# PERIPHERALS.net
KiCad netlist of a schematic drawn in Altium Designer
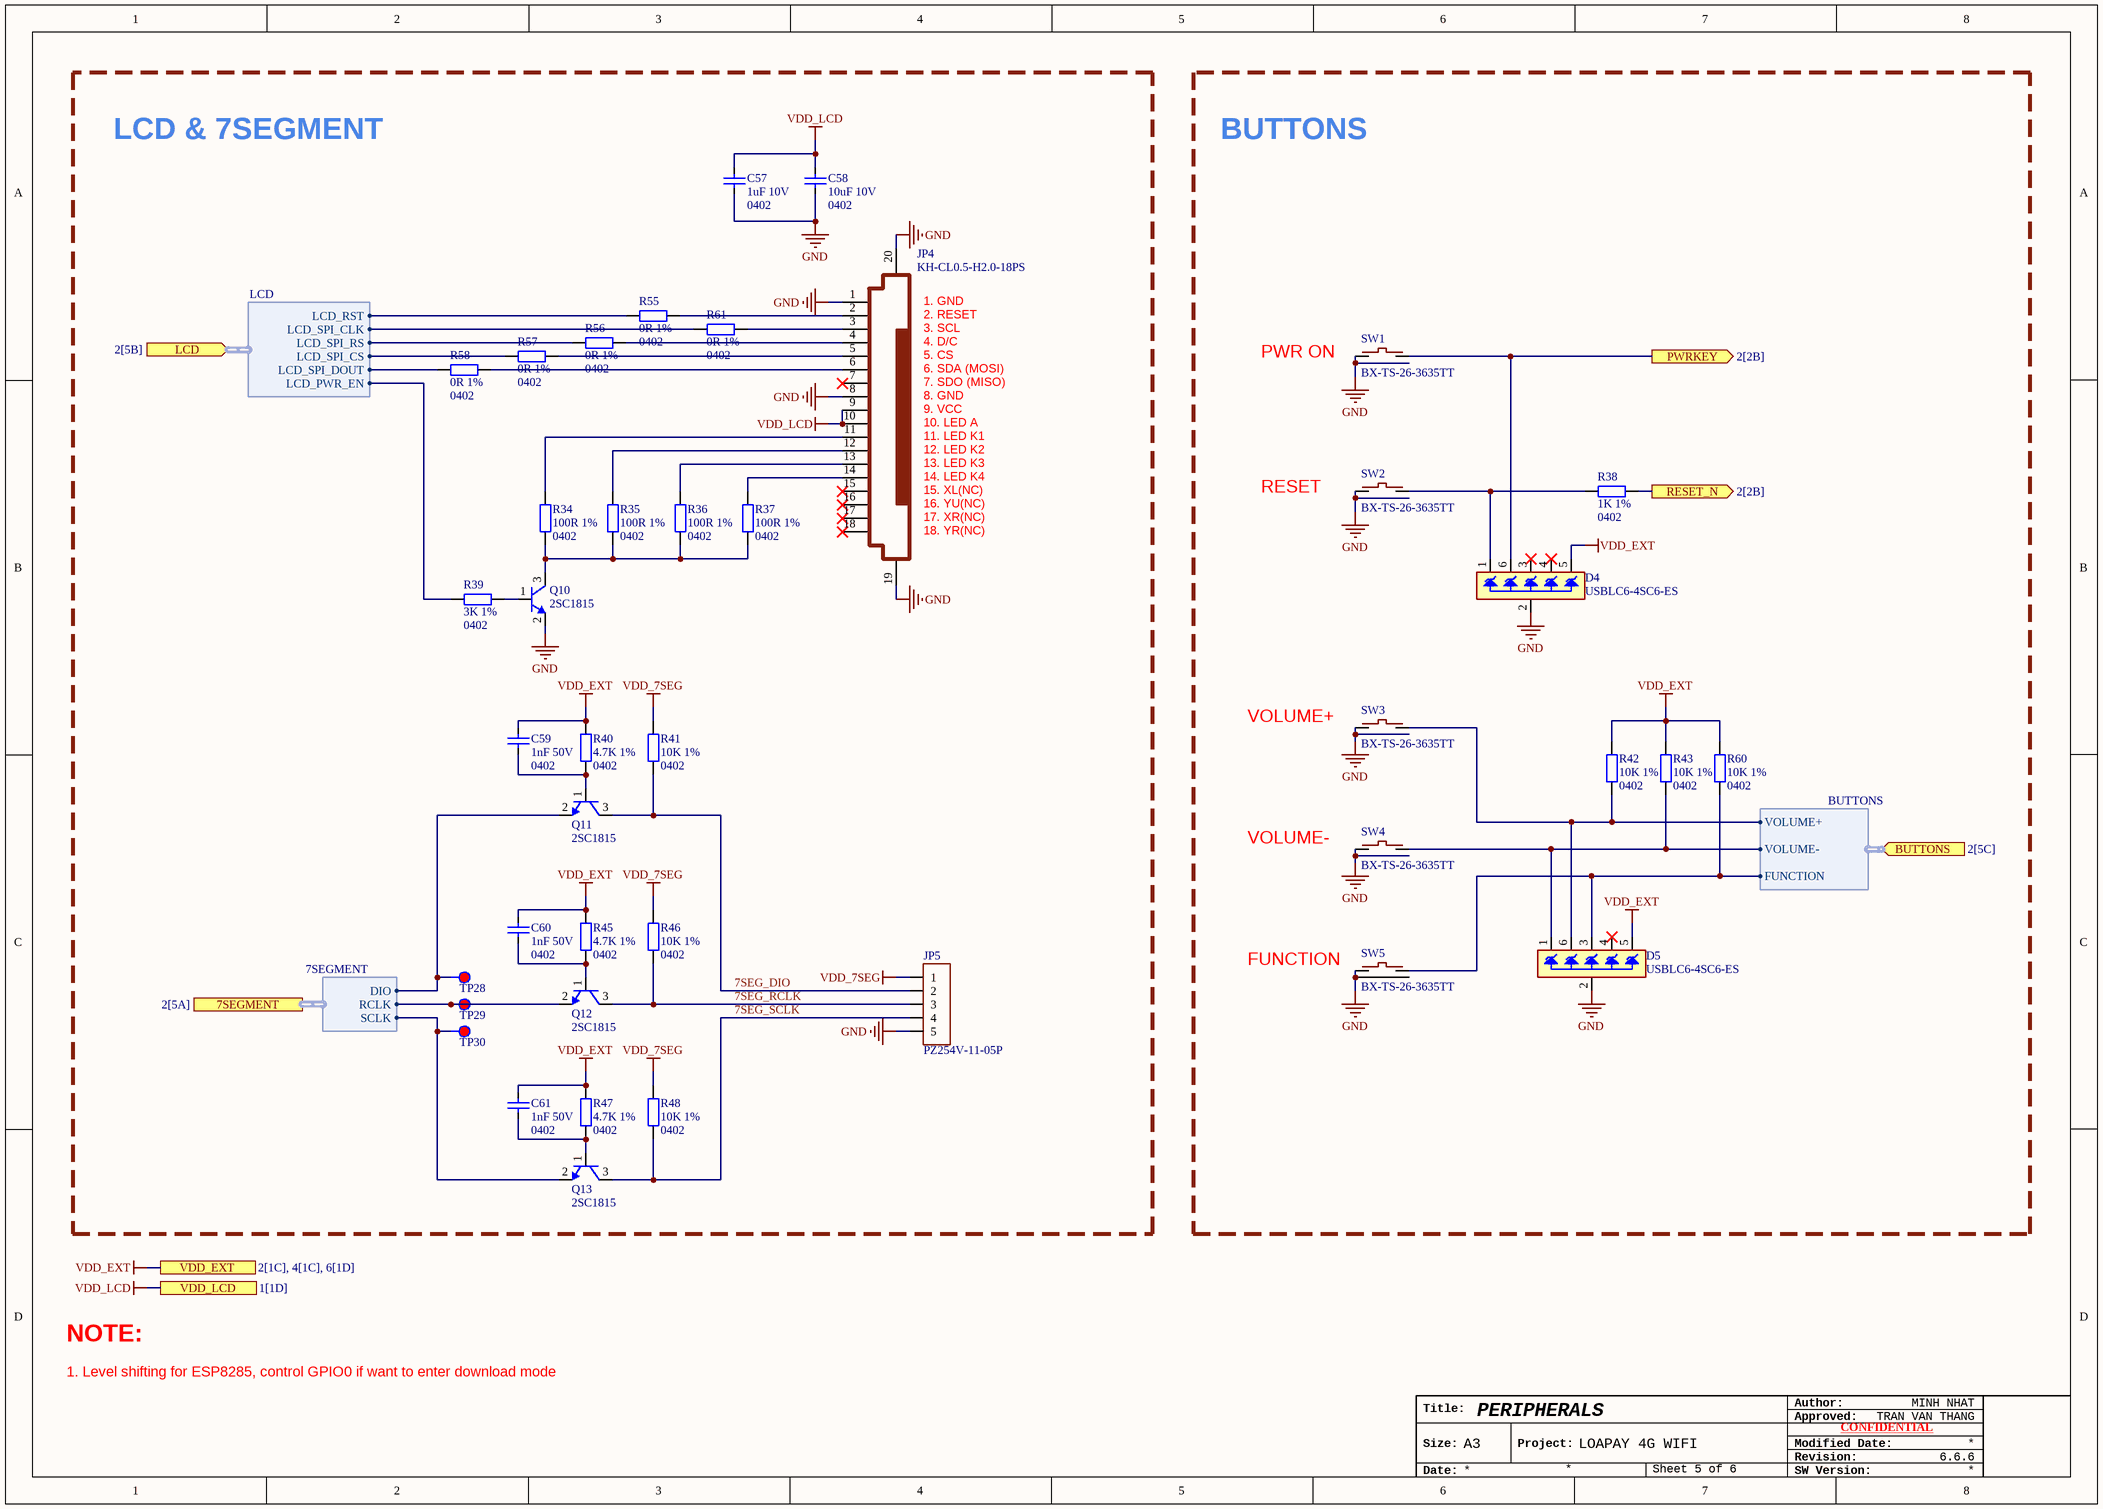
[diagram p0: PERIPHERALS.SchDoc]

(export (version "E")
  (design (tool "Eeschema 10.0.6"))
  (components
    (comp (ref "C57")
      (value "1uF 10V")
      (footprint "C0402_2")
      (description "10V 1uF X5R ±10% 0402 Multilayer Ceramic Capacitors MLCC - SMD/SMT ROHS")
      (fields
        (field (name "MANUFACTURER") "Samsung Electro-Mechanics")
        (field (name "MANUFACTURE PART NUMBER") "CL05A105KP5NNNC")
        (field (name "PACKAGE") "0402")
      )
      (libsource (lib "Capacitor") (part "C0402_MLCC_1uF_10V"))
    )
    (comp (ref "C58")
      (value "10uF 10V")
      (footprint "C0402_2")
      (description "10V 10uF X5R ±20% 0402 Multilayer Ceramic Capacitors MLCC - SMD/SMT ROHS")
      (fields
        (field (name "MANUFACTURER") "Samsung Electro-Mechanics")
        (field (name "MANUFACTURE PART NUMBER") "CL05A106MP5NUNC")
        (field (name "PACKAGE") "0402")
      )
      (libsource (lib "Capacitor") (part "C0402_MLCC_10uF_10V"))
    )
    (comp (ref "C59")
      (value "1nF 50V")
      (footprint "C0402_2")
      (description "50V 1nF X7R ±10% 0402 Multilayer Ceramic Capacitors MLCC - SMD/SMT ROHS")
      (fields
        (field (name "MANUFACTURER") "Murata Electronics")
        (field (name "MANUFACTURE PART NUMBER") "GCM155R71H102KA37J")
        (field (name "PACKAGE") "0402")
      )
      (libsource (lib "Capacitor") (part "C0402_MLCC_1nF_50V"))
    )
    (comp (ref "C60")
      (value "1nF 50V")
      (footprint "C0402_2")
      (description "50V 1nF X7R ±10% 0402 Multilayer Ceramic Capacitors MLCC - SMD/SMT ROHS")
      (fields
        (field (name "MANUFACTURER") "Murata Electronics")
        (field (name "MANUFACTURE PART NUMBER") "GCM155R71H102KA37J")
        (field (name "PACKAGE") "0402")
      )
      (libsource (lib "Capacitor") (part "C0402_MLCC_1nF_50V"))
    )
    (comp (ref "C61")
      (value "1nF 50V")
      (footprint "C0402_2")
      (description "50V 1nF X7R ±10% 0402 Multilayer Ceramic Capacitors MLCC - SMD/SMT ROHS")
      (fields
        (field (name "MANUFACTURER") "Murata Electronics")
        (field (name "MANUFACTURE PART NUMBER") "GCM155R71H102KA37J")
        (field (name "PACKAGE") "0402")
      )
      (libsource (lib "Capacitor") (part "C0402_MLCC_1nF_50V"))
    )
    (comp (ref "D4")
      (value "USBLC6-4SC6-ES")
      (footprint "D_SOT23-6")
      (description "4.5A 60W 12V 6V Unidirectional 5V SOT23-6 ESD and Surge Protection (TVS/ESD) ROHS")
      (fields (field (name "MANUFACTURER") "ElecSuper") (field (name "LCSC PART") "C5180279"))
      (libsource (lib "Diode") (part "USBLC6-4SC6-ES"))
    )
    (comp (ref "D5")
      (value "USBLC6-4SC6-ES")
      (footprint "D_SOT23-6")
      (description "4.5A 60W 12V 6V Unidirectional 5V SOT23-6 ESD and Surge Protection (TVS/ESD) ROHS")
      (fields (field (name "MANUFACTURER") "ElecSuper") (field (name "LCSC PART") "C5180279"))
      (libsource (lib "Diode") (part "USBLC6-4SC6-ES"))
    )
    (comp (ref "JP4")
      (value "KH-CL0.5-H2.0-18PS")
      (footprint "FPC-SMD-18P-TOP")
      (fields (field (name "MANUFACTURER") "Shenzhen Kinghelm Elec") (field (name "LCSC PART") "C2828051"))
      (libsource (lib "Connector") (part "KH-CL0.5-H2.0-18PS"))
    )
    (comp (ref "JP5")
      (value "PZ254V-11-05P")
      (footprint "JP5_M_SMD - 2")
      (fields (field (name "MANUFACTURER") "XFCN") (field (name "LCSC PART") "C492404"))
      (libsource (lib "Connector") (part "XFCN PZ254V-11-05P"))
    )
    (comp (ref "Q10")
      (value "2SC1815")
      (footprint "TF_SOT_23_3")
      (description "50V 200mW 200@2mA,6V 150mA NPN SOT-23 Bipolar (BJT) ROHS")
      (fields (field (name "MANUFACTURER") "Guangdong Hottech") (field (name "LCSC PART") "C181171"))
      (libsource (lib "Trans_Fet") (part "2SC1815"))
    )
    (comp (ref "Q11")
      (value "2SC1815")
      (footprint "TF_SOT_23_3")
      (description "50V 200mW 200@2mA,6V 150mA NPN SOT-23 Bipolar (BJT) ROHS")
      (fields (field (name "MANUFACTURER") "Guangdong Hottech") (field (name "LCSC PART") "C181171"))
      (libsource (lib "Trans_Fet") (part "2SC1815"))
    )
    (comp (ref "Q12")
      (value "2SC1815")
      (footprint "TF_SOT_23_3")
      (description "50V 200mW 200@2mA,6V 150mA NPN SOT-23 Bipolar (BJT) ROHS")
      (fields (field (name "MANUFACTURER") "Guangdong Hottech") (field (name "LCSC PART") "C181171"))
      (libsource (lib "Trans_Fet") (part "2SC1815"))
    )
    (comp (ref "Q13")
      (value "2SC1815")
      (footprint "TF_SOT_23_3")
      (description "50V 200mW 200@2mA,6V 150mA NPN SOT-23 Bipolar (BJT) ROHS")
      (fields (field (name "MANUFACTURER") "Guangdong Hottech") (field (name "LCSC PART") "C181171"))
      (libsource (lib "Trans_Fet") (part "2SC1815"))
    )
    (comp (ref "R34")
      (value "100R 1%")
      (footprint "RES_SMD_0402")
      (fields
        (field (name "MANUFACTURER") "YAGEO")
        (field (name "MANUFACTURE PART NUMBER") "AC0402FR-13100RL")
        (field (name "TOLERANCE") "±1%")
        (field (name "PACKAGE") "0402")
      )
      (libsource (lib "Resistor") (part "R0402_100R"))
    )
    (comp (ref "R35")
      (value "100R 1%")
      (footprint "RES_SMD_0402")
      (fields
        (field (name "MANUFACTURER") "YAGEO")
        (field (name "MANUFACTURE PART NUMBER") "AC0402FR-13100RL")
        (field (name "TOLERANCE") "±1%")
        (field (name "PACKAGE") "0402")
      )
      (libsource (lib "Resistor") (part "R0402_100R"))
    )
    (comp (ref "R36")
      (value "100R 1%")
      (footprint "RES_SMD_0402")
      (fields
        (field (name "MANUFACTURER") "YAGEO")
        (field (name "MANUFACTURE PART NUMBER") "AC0402FR-13100RL")
        (field (name "TOLERANCE") "±1%")
        (field (name "PACKAGE") "0402")
      )
      (libsource (lib "Resistor") (part "R0402_100R"))
    )
    (comp (ref "R37")
      (value "100R 1%")
      (footprint "RES_SMD_0402")
      (fields
        (field (name "MANUFACTURER") "YAGEO")
        (field (name "MANUFACTURE PART NUMBER") "AC0402FR-13100RL")
        (field (name "TOLERANCE") "±1%")
        (field (name "PACKAGE") "0402")
      )
      (libsource (lib "Resistor") (part "R0402_100R"))
    )
    (comp (ref "R38")
      (value "1K 1%")
      (footprint "RES_SMD_0402")
      (description "1 kOhms ±1% 0.063W, 1/16W Chip Resistor 0402 (1005 Metric) Moisture Resistant Thick Film")
      (fields
        (field (name "MANUFACTURER") "YAGEO")
        (field (name "MANUFACTURE PART NUMBER") "RC0402FR-071KL")
        (field (name "PACKAGE") "0402")
      )
      (libsource (lib "Resistor") (part "R0402_1K"))
    )
    (comp (ref "R39")
      (value "3K 1%")
      (footprint "RES_SMD_0402")
      (fields
        (field (name "MANUFACTURER") "YAGEO")
        (field (name "MANUFACTURE PART NUMBER") "AC0402FR-073KL")
        (field (name "TOLERANCE") "±1%")
        (field (name "PACKAGE") "0402")
      )
      (libsource (lib "Resistor") (part "R0402_3K"))
    )
    (comp (ref "R40")
      (value "4.7K 1%")
      (footprint "RES_SMD_0402")
      (description "4.7 kOhms ±1% 0.063W, 1/16W Chip Resistor 0402 (1005 Metric) Thick Film")
      (fields
        (field (name "MANUFACTURER") "YAGEO")
        (field (name "MANUFACTURE PART NUMBER") "RC0402FR-074K7P")
        (field (name "PACKAGE") "0402")
      )
      (libsource (lib "Resistor") (part "R0402_4.7K"))
    )
    (comp (ref "R41")
      (value "10K 1%")
      (footprint "RES_SMD_0402")
      (description "10 kOhms ±1% 0.063W, 1/16W Chip Resistor 0402 (1005 Metric) Moisture Resistant Thick Film")
      (fields
        (field (name "MANUFACTURER") "YAGEO")
        (field (name "MANUFACTURE PART NUMBER") "RC0402FR-0710KL")
        (field (name "PACKAGE") "0402")
      )
      (libsource (lib "Resistor") (part "R0402_10K"))
    )
    (comp (ref "R42")
      (value "10K 1%")
      (footprint "RES_SMD_0402")
      (description "10 kOhms ±1% 0.063W, 1/16W Chip Resistor 0402 (1005 Metric) Moisture Resistant Thick Film")
      (fields
        (field (name "MANUFACTURER") "YAGEO")
        (field (name "MANUFACTURE PART NUMBER") "RC0402FR-0710KL")
        (field (name "PACKAGE") "0402")
      )
      (libsource (lib "Resistor") (part "R0402_10K"))
    )
    (comp (ref "R43")
      (value "10K 1%")
      (footprint "RES_SMD_0402")
      (description "10 kOhms ±1% 0.063W, 1/16W Chip Resistor 0402 (1005 Metric) Moisture Resistant Thick Film")
      (fields
        (field (name "MANUFACTURER") "YAGEO")
        (field (name "MANUFACTURE PART NUMBER") "RC0402FR-0710KL")
        (field (name "PACKAGE") "0402")
      )
      (libsource (lib "Resistor") (part "R0402_10K"))
    )
    (comp (ref "R45")
      (value "4.7K 1%")
      (footprint "RES_SMD_0402")
      (description "4.7 kOhms ±1% 0.063W, 1/16W Chip Resistor 0402 (1005 Metric) Thick Film")
      (fields
        (field (name "MANUFACTURER") "YAGEO")
        (field (name "MANUFACTURE PART NUMBER") "RC0402FR-074K7P")
        (field (name "PACKAGE") "0402")
      )
      (libsource (lib "Resistor") (part "R0402_4.7K"))
    )
    (comp (ref "R46")
      (value "10K 1%")
      (footprint "RES_SMD_0402")
      (description "10 kOhms ±1% 0.063W, 1/16W Chip Resistor 0402 (1005 Metric) Moisture Resistant Thick Film")
      (fields
        (field (name "MANUFACTURER") "YAGEO")
        (field (name "MANUFACTURE PART NUMBER") "RC0402FR-0710KL")
        (field (name "PACKAGE") "0402")
      )
      (libsource (lib "Resistor") (part "R0402_10K"))
    )
    (comp (ref "R47")
      (value "4.7K 1%")
      (footprint "RES_SMD_0402")
      (description "4.7 kOhms ±1% 0.063W, 1/16W Chip Resistor 0402 (1005 Metric) Thick Film")
      (fields
        (field (name "MANUFACTURER") "YAGEO")
        (field (name "MANUFACTURE PART NUMBER") "RC0402FR-074K7P")
        (field (name "PACKAGE") "0402")
      )
      (libsource (lib "Resistor") (part "R0402_4.7K"))
    )
    (comp (ref "R48")
      (value "10K 1%")
      (footprint "RES_SMD_0402")
      (description "10 kOhms ±1% 0.063W, 1/16W Chip Resistor 0402 (1005 Metric) Moisture Resistant Thick Film")
      (fields
        (field (name "MANUFACTURER") "YAGEO")
        (field (name "MANUFACTURE PART NUMBER") "RC0402FR-0710KL")
        (field (name "PACKAGE") "0402")
      )
      (libsource (lib "Resistor") (part "R0402_10K"))
    )
    (comp (ref "R55")
      (value "0R 1%")
      (footprint "RES_SMD_0402")
      (description "0 Ohms Jumper Chip Resistor 0402 (1005 Metric) Moisture Resistant Thick Film")
      (fields
        (field (name "MANUFACTURER") "YAGEO")
        (field (name "MANUFACTURE PART NUMBER") "RC0402JR-070RL")
        (field (name "PACKAGE") "0402")
      )
      (libsource (lib "Resistor") (part "R0402_0R"))
    )
    (comp (ref "R56")
      (value "0R 1%")
      (footprint "RES_SMD_0402")
      (description "0 Ohms Jumper Chip Resistor 0402 (1005 Metric) Moisture Resistant Thick Film")
      (fields
        (field (name "MANUFACTURER") "YAGEO")
        (field (name "MANUFACTURE PART NUMBER") "RC0402JR-070RL")
        (field (name "PACKAGE") "0402")
      )
      (libsource (lib "Resistor") (part "R0402_0R"))
    )
    (comp (ref "R57")
      (value "0R 1%")
      (footprint "RES_SMD_0402")
      (description "0 Ohms Jumper Chip Resistor 0402 (1005 Metric) Moisture Resistant Thick Film")
      (fields
        (field (name "MANUFACTURER") "YAGEO")
        (field (name "MANUFACTURE PART NUMBER") "RC0402JR-070RL")
        (field (name "PACKAGE") "0402")
      )
      (libsource (lib "Resistor") (part "R0402_0R"))
    )
    (comp (ref "R58")
      (value "0R 1%")
      (footprint "RES_SMD_0402")
      (description "0 Ohms Jumper Chip Resistor 0402 (1005 Metric) Moisture Resistant Thick Film")
      (fields
        (field (name "MANUFACTURER") "YAGEO")
        (field (name "MANUFACTURE PART NUMBER") "RC0402JR-070RL")
        (field (name "PACKAGE") "0402")
      )
      (libsource (lib "Resistor") (part "R0402_0R"))
    )
    (comp (ref "R60")
      (value "10K 1%")
      (footprint "RES_SMD_0402")
      (description "10 kOhms ±1% 0.063W, 1/16W Chip Resistor 0402 (1005 Metric) Moisture Resistant Thick Film")
      (fields
        (field (name "MANUFACTURER") "YAGEO")
        (field (name "MANUFACTURE PART NUMBER") "RC0402FR-0710KL")
        (field (name "PACKAGE") "0402")
      )
      (libsource (lib "Resistor") (part "R0402_10K"))
    )
    (comp (ref "R61")
      (value "0R 1%")
      (footprint "RES_SMD_0402")
      (description "0 Ohms Jumper Chip Resistor 0402 (1005 Metric) Moisture Resistant Thick Film")
      (fields
        (field (name "MANUFACTURER") "YAGEO")
        (field (name "MANUFACTURE PART NUMBER") "RC0402JR-070RL")
        (field (name "PACKAGE") "0402")
      )
      (libsource (lib "Resistor") (part "R0402_0R"))
    )
    (comp (ref "SW1")
      (value "BX-TS-26-3635TT")
      (footprint "BX-TS-26-3635TT")
      (fields (field (name "MANUFACTURER") "Bossie") (field (name "MANUFACTURE PART NUMBER") "C18078107"))
      (libsource (lib "Switch") (part "BX-TS-26-3635TT"))
    )
    (comp (ref "SW2")
      (value "BX-TS-26-3635TT")
      (footprint "BX-TS-26-3635TT")
      (fields (field (name "MANUFACTURER") "Bossie") (field (name "MANUFACTURE PART NUMBER") "C18078107"))
      (libsource (lib "Switch") (part "BX-TS-26-3635TT"))
    )
    (comp (ref "SW3")
      (value "BX-TS-26-3635TT")
      (footprint "BX-TS-26-3635TT")
      (fields (field (name "MANUFACTURER") "Bossie") (field (name "MANUFACTURE PART NUMBER") "C18078107"))
      (libsource (lib "Switch") (part "BX-TS-26-3635TT"))
    )
    (comp (ref "SW4")
      (value "BX-TS-26-3635TT")
      (footprint "BX-TS-26-3635TT")
      (fields (field (name "MANUFACTURER") "Bossie") (field (name "MANUFACTURE PART NUMBER") "C18078107"))
      (libsource (lib "Switch") (part "BX-TS-26-3635TT"))
    )
    (comp (ref "SW5")
      (value "BX-TS-26-3635TT")
      (footprint "BX-TS-26-3635TT")
      (fields (field (name "MANUFACTURER") "Bossie") (field (name "MANUFACTURE PART NUMBER") "C18078107"))
      (libsource (lib "Switch") (part "BX-TS-26-3635TT"))
    )
    (comp (ref "TP28")
      (value "Test Point")
      (footprint "TEST_POINT")
      (libsource (lib "Connector") (part "TEST_POINT"))
    )
    (comp (ref "TP29")
      (value "Test Point")
      (footprint "TEST_POINT")
      (libsource (lib "Connector") (part "TEST_POINT"))
    )
    (comp (ref "TP30")
      (value "Test Point")
      (footprint "TEST_POINT")
      (libsource (lib "Connector") (part "TEST_POINT"))
    )
  )
  (nets
    (net (code "4") (name "/7SEG_DIO") (class "Default")
      (node (ref "JP5") (pin "2") (pinfunction "2_2") (pintype "passive"))
      (node (ref "Q11") (pin "3") (pinfunction "C_3") (pintype "passive"))
      (node (ref "R41") (pin "1") (pinfunction "1_1") (pintype "passive"))
    )
    (net (code "5") (name "/7SEG_RCLK") (class "Default")
      (node (ref "JP5") (pin "3") (pinfunction "3_3") (pintype "passive"))
      (node (ref "Q12") (pin "3") (pinfunction "C_3") (pintype "passive"))
      (node (ref "R46") (pin "1") (pinfunction "1_1") (pintype "passive"))
    )
    (net (code "6") (name "/7SEG_SCLK") (class "Default")
      (node (ref "JP5") (pin "4") (pinfunction "4_4") (pintype "passive"))
      (node (ref "Q13") (pin "3") (pinfunction "C_3") (pintype "passive"))
      (node (ref "R48") (pin "1") (pinfunction "1_1") (pintype "passive"))
    )
    (net (code "7") (name "/DIO") (class "Default")
      (node (ref "Q11") (pin "2") (pinfunction "E_2") (pintype "passive"))
      (node (ref "TP28") (pin "1") (pinfunction "1_1") (pintype "passive"))
    )
    (net (code "8") (name "/FUNCTION") (class "Default")
      (node (ref "D5") (pin "3") (pinfunction "3_3") (pintype "passive"))
      (node (ref "R60") (pin "1") (pinfunction "1_1") (pintype "passive"))
      (node (ref "SW5") (pin "2") (pinfunction "2_2") (pintype "passive"))
    )
    (net (code "9") (name "/LCD_PWR_EN") (class "Default")
      (node (ref "R39") (pin "1") (pinfunction "1_1") (pintype "passive"))
    )
    (net (code "10") (name "/LCD_RST") (class "Default")
      (node (ref "R55") (pin "1") (pinfunction "1_1") (pintype "passive"))
    )
    (net (code "11") (name "/LCD_SPI_CLK") (class "Default")
      (node (ref "R61") (pin "1") (pinfunction "1_1") (pintype "passive"))
    )
    (net (code "12") (name "/LCD_SPI_CS") (class "Default")
      (node (ref "R57") (pin "1") (pinfunction "1_1") (pintype "passive"))
    )
    (net (code "13") (name "/LCD_SPI_DOUT") (class "Default")
      (node (ref "R58") (pin "1") (pinfunction "1_1") (pintype "passive"))
    )
    (net (code "14") (name "/LCD_SPI_RS") (class "Default")
      (node (ref "R56") (pin "1") (pinfunction "1_1") (pintype "passive"))
    )
    (net (code "15") (name "/PWRKEY") (class "Default")
      (node (ref "D4") (pin "6") (pinfunction "6_6") (pintype "passive"))
      (node (ref "SW1") (pin "2") (pinfunction "2_2") (pintype "passive"))
    )
    (net (code "16") (name "/RCLK") (class "Default")
      (node (ref "Q12") (pin "2") (pinfunction "E_2") (pintype "passive"))
      (node (ref "TP29") (pin "1") (pinfunction "1_1") (pintype "passive"))
    )
    (net (code "17") (name "/RESET_N") (class "Default")
      (node (ref "R38") (pin "2") (pinfunction "2_2") (pintype "passive"))
    )
    (net (code "18") (name "/SCLK") (class "Default")
      (node (ref "Q13") (pin "2") (pinfunction "E_2") (pintype "passive"))
      (node (ref "TP30") (pin "1") (pinfunction "1_1") (pintype "passive"))
    )
    (net (code "19") (name "/VOLUME+") (class "Default")
      (node (ref "D5") (pin "6") (pinfunction "6_6") (pintype "passive"))
      (node (ref "R42") (pin "1") (pinfunction "1_1") (pintype "passive"))
      (node (ref "SW3") (pin "1") (pinfunction "1_1") (pintype "passive"))
    )
    (net (code "20") (name "/VOLUME-") (class "Default")
      (node (ref "D5") (pin "1") (pinfunction "1_1") (pintype "passive"))
      (node (ref "R43") (pin "1") (pinfunction "1_1") (pintype "passive"))
      (node (ref "SW4") (pin "1") (pinfunction "1_1") (pintype "passive"))
    )
    (net (code "24") (name "GND") (class "Default")
      (node (ref "C57") (pin "1") (pinfunction "1_1") (pintype "passive"))
      (node (ref "C58") (pin "1") (pinfunction "1_1") (pintype "passive"))
      (node (ref "D4") (pin "2") (pinfunction "2_2") (pintype "passive"))
      (node (ref "D5") (pin "2") (pinfunction "2_2") (pintype "passive"))
      (node (ref "JP4") (pin "1") (pinfunction "1_1") (pintype "passive"))
      (node (ref "JP4") (pin "19") (pinfunction "19_19") (pintype "passive"))
      (node (ref "JP4") (pin "20") (pinfunction "20_20") (pintype "passive"))
      (node (ref "JP4") (pin "8") (pinfunction "8_8") (pintype "passive"))
      (node (ref "JP5") (pin "5") (pinfunction "5_5") (pintype "passive"))
      (node (ref "Q10") (pin "2") (pinfunction "E_2") (pintype "passive"))
      (node (ref "SW1") (pin "1") (pinfunction "1_1") (pintype "passive"))
      (node (ref "SW1") (pin "3") (pinfunction "3_3") (pintype "passive"))
      (node (ref "SW1") (pin "4") (pinfunction "4_4") (pintype "passive"))
      (node (ref "SW2") (pin "1") (pinfunction "1_1") (pintype "passive"))
      (node (ref "SW2") (pin "3") (pinfunction "3_3") (pintype "passive"))
      (node (ref "SW2") (pin "4") (pinfunction "4_4") (pintype "passive"))
      (node (ref "SW3") (pin "2") (pinfunction "2_2") (pintype "passive"))
      (node (ref "SW3") (pin "3") (pinfunction "3_3") (pintype "passive"))
      (node (ref "SW3") (pin "4") (pinfunction "4_4") (pintype "passive"))
      (node (ref "SW4") (pin "2") (pinfunction "2_2") (pintype "passive"))
      (node (ref "SW4") (pin "3") (pinfunction "3_3") (pintype "passive"))
      (node (ref "SW4") (pin "4") (pinfunction "4_4") (pintype "passive"))
      (node (ref "SW5") (pin "1") (pinfunction "1_1") (pintype "passive"))
      (node (ref "SW5") (pin "4") (pinfunction "4_4") (pintype "passive"))
    )
    (net (code "25") (name "Net-(D4-Pad1)") (class "Default")
      (node (ref "D4") (pin "1") (pinfunction "1_1") (pintype "passive"))
      (node (ref "R38") (pin "1") (pinfunction "1_1") (pintype "passive"))
      (node (ref "SW2") (pin "2") (pinfunction "2_2") (pintype "passive"))
    )
    (net (code "26") (name "Net-(JP4-Pad2)") (class "Default")
      (node (ref "JP4") (pin "2") (pinfunction "2_2") (pintype "passive"))
      (node (ref "R55") (pin "2") (pinfunction "2_2") (pintype "passive"))
    )
    (net (code "27") (name "Net-(JP4-Pad3)") (class "Default")
      (node (ref "JP4") (pin "3") (pinfunction "3_3") (pintype "passive"))
      (node (ref "R61") (pin "2") (pinfunction "2_2") (pintype "passive"))
    )
    (net (code "28") (name "Net-(JP4-Pad4)") (class "Default")
      (node (ref "JP4") (pin "4") (pinfunction "4_4") (pintype "passive"))
      (node (ref "R56") (pin "2") (pinfunction "2_2") (pintype "passive"))
    )
    (net (code "29") (name "Net-(JP4-Pad5)") (class "Default")
      (node (ref "JP4") (pin "5") (pinfunction "5_5") (pintype "passive"))
      (node (ref "R57") (pin "2") (pinfunction "2_2") (pintype "passive"))
    )
    (net (code "30") (name "Net-(JP4-Pad6)") (class "Default")
      (node (ref "JP4") (pin "6") (pinfunction "6_6") (pintype "passive"))
      (node (ref "R58") (pin "2") (pinfunction "2_2") (pintype "passive"))
    )
    (net (code "31") (name "Net-(JP4-Pad11)") (class "Default")
      (node (ref "JP4") (pin "11") (pinfunction "11_11") (pintype "passive"))
      (node (ref "R34") (pin "2") (pinfunction "2_2") (pintype "passive"))
    )
    (net (code "32") (name "Net-(JP4-Pad12)") (class "Default")
      (node (ref "JP4") (pin "12") (pinfunction "12_12") (pintype "passive"))
      (node (ref "R35") (pin "2") (pinfunction "2_2") (pintype "passive"))
    )
    (net (code "33") (name "Net-(JP4-Pad13)") (class "Default")
      (node (ref "JP4") (pin "13") (pinfunction "13_13") (pintype "passive"))
      (node (ref "R36") (pin "2") (pinfunction "2_2") (pintype "passive"))
    )
    (net (code "34") (name "Net-(JP4-Pad14)") (class "Default")
      (node (ref "JP4") (pin "14") (pinfunction "14_14") (pintype "passive"))
      (node (ref "R37") (pin "2") (pinfunction "2_2") (pintype "passive"))
    )
    (net (code "35") (name "Net-(Q10-B)") (class "Default")
      (node (ref "Q10") (pin "1") (pinfunction "B_1") (pintype "passive"))
      (node (ref "R39") (pin "2") (pinfunction "2_2") (pintype "passive"))
    )
    (net (code "36") (name "Net-(Q10-C)") (class "Default")
      (node (ref "Q10") (pin "3") (pinfunction "C_3") (pintype "passive"))
      (node (ref "R34") (pin "1") (pinfunction "1_1") (pintype "passive"))
      (node (ref "R35") (pin "1") (pinfunction "1_1") (pintype "passive"))
      (node (ref "R36") (pin "1") (pinfunction "1_1") (pintype "passive"))
      (node (ref "R37") (pin "1") (pinfunction "1_1") (pintype "passive"))
    )
    (net (code "37") (name "Net-(Q11-B)") (class "Default")
      (node (ref "C59") (pin "1") (pinfunction "1_1") (pintype "passive"))
      (node (ref "Q11") (pin "1") (pinfunction "B_1") (pintype "passive"))
      (node (ref "R40") (pin "1") (pinfunction "1_1") (pintype "passive"))
    )
    (net (code "38") (name "Net-(Q12-B)") (class "Default")
      (node (ref "C60") (pin "1") (pinfunction "1_1") (pintype "passive"))
      (node (ref "Q12") (pin "1") (pinfunction "B_1") (pintype "passive"))
      (node (ref "R45") (pin "1") (pinfunction "1_1") (pintype "passive"))
    )
    (net (code "39") (name "Net-(Q13-B)") (class "Default")
      (node (ref "C61") (pin "1") (pinfunction "1_1") (pintype "passive"))
      (node (ref "Q13") (pin "1") (pinfunction "B_1") (pintype "passive"))
      (node (ref "R47") (pin "1") (pinfunction "1_1") (pintype "passive"))
    )
    (net (code "40") (name "VDD_7SEG") (class "Default")
      (node (ref "JP5") (pin "1") (pinfunction "1_1") (pintype "passive"))
      (node (ref "R41") (pin "2") (pinfunction "2_2") (pintype "passive"))
      (node (ref "R46") (pin "2") (pinfunction "2_2") (pintype "passive"))
      (node (ref "R48") (pin "2") (pinfunction "2_2") (pintype "passive"))
    )
    (net (code "41") (name "VDD_EXT") (class "Default")
      (node (ref "C59") (pin "2") (pinfunction "2_2") (pintype "passive"))
      (node (ref "C60") (pin "2") (pinfunction "2_2") (pintype "passive"))
      (node (ref "C61") (pin "2") (pinfunction "2_2") (pintype "passive"))
      (node (ref "D4") (pin "5") (pinfunction "5_5") (pintype "passive"))
      (node (ref "D5") (pin "5") (pinfunction "5_5") (pintype "passive"))
      (node (ref "R40") (pin "2") (pinfunction "2_2") (pintype "passive"))
      (node (ref "R42") (pin "2") (pinfunction "2_2") (pintype "passive"))
      (node (ref "R43") (pin "2") (pinfunction "2_2") (pintype "passive"))
      (node (ref "R45") (pin "2") (pinfunction "2_2") (pintype "passive"))
      (node (ref "R47") (pin "2") (pinfunction "2_2") (pintype "passive"))
      (node (ref "R60") (pin "2") (pinfunction "2_2") (pintype "passive"))
    )
    (net (code "42") (name "VDD_LCD") (class "Default")
      (node (ref "C57") (pin "2") (pinfunction "2_2") (pintype "passive"))
      (node (ref "C58") (pin "2") (pinfunction "2_2") (pintype "passive"))
      (node (ref "JP4") (pin "10") (pinfunction "10_10") (pintype "passive"))
      (node (ref "JP4") (pin "9") (pinfunction "9_9") (pintype "passive"))
    )
    (net (code "43") (name "unconnected-(D4-Pad3)") (class "Default")
      (node (ref "D4") (pin "3") (pinfunction "3_3") (pintype "passive+no_connect"))
    )
    (net (code "44") (name "unconnected-(D4-Pad4)") (class "Default")
      (node (ref "D4") (pin "4") (pinfunction "4_4") (pintype "passive+no_connect"))
    )
    (net (code "45") (name "unconnected-(D5-Pad4)") (class "Default")
      (node (ref "D5") (pin "4") (pinfunction "4_4") (pintype "passive+no_connect"))
    )
    (net (code "46") (name "unconnected-(JP4-Pad7)") (class "Default")
      (node (ref "JP4") (pin "7") (pinfunction "7_7") (pintype "passive+no_connect"))
    )
    (net (code "47") (name "unconnected-(JP4-Pad15)") (class "Default")
      (node (ref "JP4") (pin "15") (pinfunction "15_15") (pintype "passive+no_connect"))
    )
    (net (code "48") (name "unconnected-(JP4-Pad16)") (class "Default")
      (node (ref "JP4") (pin "16") (pinfunction "16_16") (pintype "passive+no_connect"))
    )
    (net (code "49") (name "unconnected-(JP4-Pad17)") (class "Default")
      (node (ref "JP4") (pin "17") (pinfunction "17_17") (pintype "passive+no_connect"))
    )
    (net (code "50") (name "unconnected-(JP4-Pad18)") (class "Default")
      (node (ref "JP4") (pin "18") (pinfunction "18_18") (pintype "passive+no_connect"))
    )
    (net (code "51") (name "unconnected-(SW5-Pad3)") (class "Default")
      (node (ref "SW5") (pin "3") (pinfunction "3_3") (pintype "passive"))
    )
  )
)
